# ImprovedBlackPill.net
KiCad netlist of a schematic drawn in Altium Designer
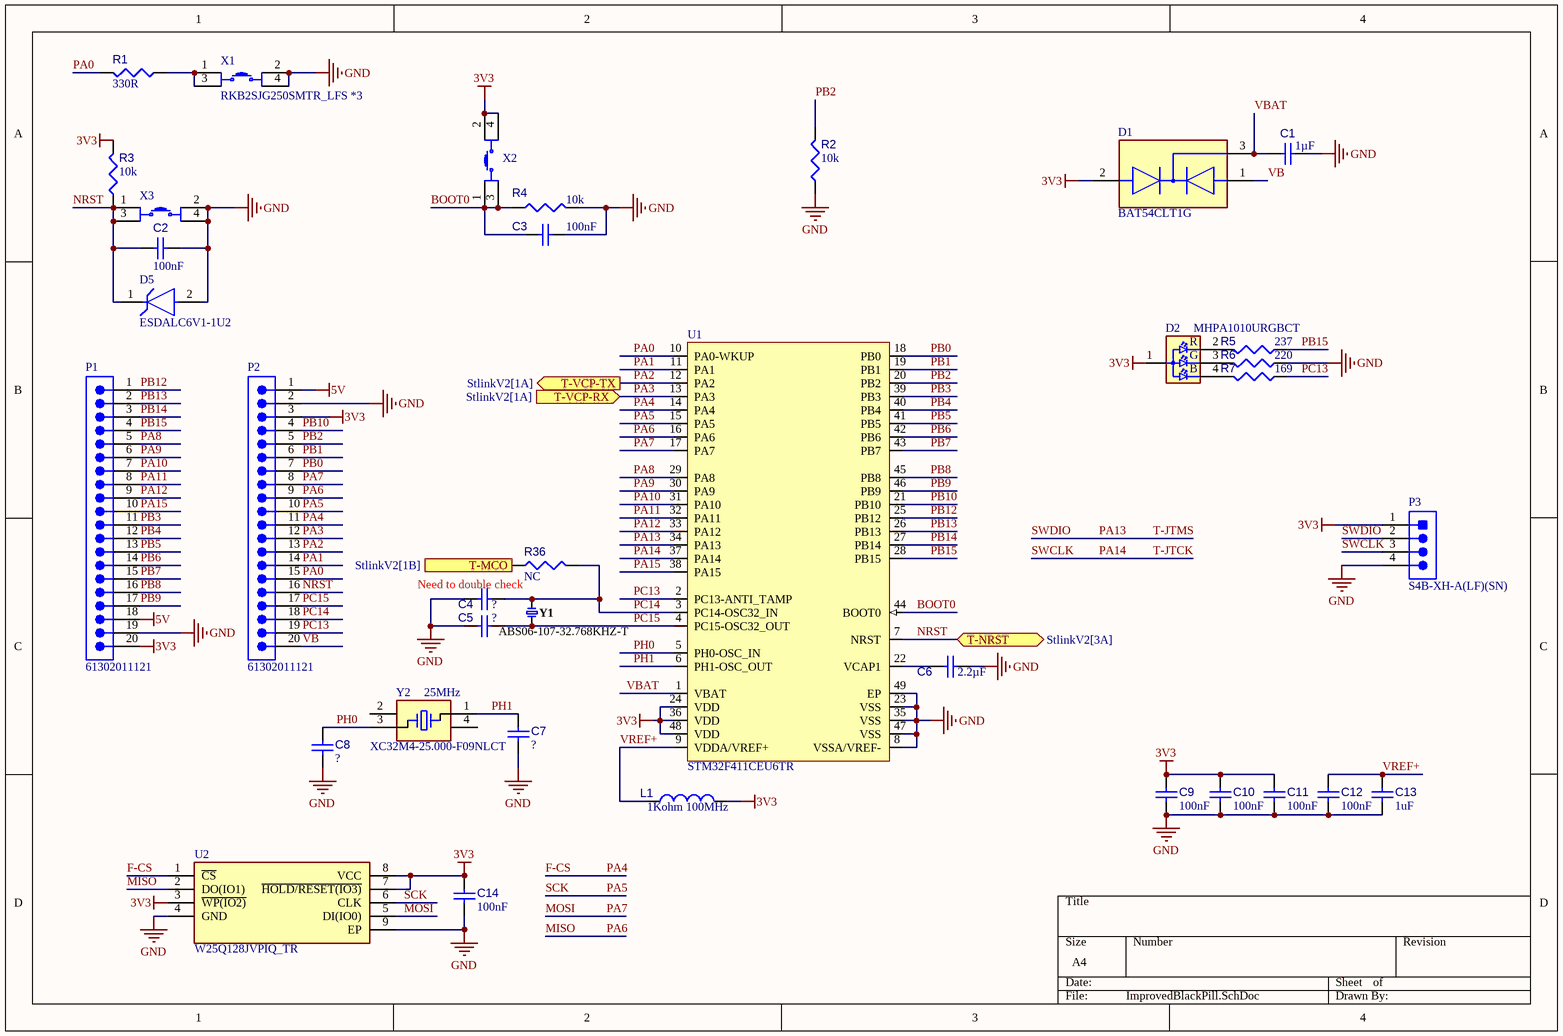
[diagram p0: ImprovedBlackPill.SchDoc]

(export (version "E")
  (design (tool "Eeschema 10.0.6"))
  (components
    (comp (ref "C1")
      (value "1µF")
      (footprint "CAPC1005X55X25ML05T10")
      (description "Chip Capacitor, 1 uF, +/- 10%, 6.3 V, 0402 (1005 Metric)")
      (fields (field (name "TOLERANCE") "10%") (field (name "Comment") "Capacitor 1 uF +/- 10% 6.3 V 0402"))
      (libsource (lib "Fei Han") (part "CAP-NP-2"))
    )
    (comp (ref "C2")
      (value "100nF")
      (footprint "CAPC1005X55X25ML05T05")
      (description "Chip Capacitor, 10 pF, +/- 5%, 50 V, 0402 (1005 Metric)")
      (fields (field (name "TOLERANCE") "5%") (field (name "Comment") "Capacitor 10 pF +/- 5% 50 V 0402"))
      (libsource (lib "Fei Han") (part "CAP-NP-2"))
    )
    (comp (ref "C3")
      (value "100nF")
      (footprint "CAPC1005X55X25ML05T05")
      (description "Chip Capacitor, 10 pF, +/- 5%, 50 V, 0402 (1005 Metric)")
      (fields (field (name "TOLERANCE") "5%") (field (name "Comment") "Capacitor 10 pF +/- 5% 50 V 0402"))
      (libsource (lib "Fei Han") (part "CAP-NP-2"))
    )
    (comp (ref "C4")
      (value "?")
      (footprint "CAPC1005X55X25ML05T05")
      (description "Chip Capacitor, 10 pF, +/- 5%, 50 V, 0402 (1005 Metric)")
      (fields (field (name "TOLERANCE") "5%") (field (name "Comment") "Capacitor 10 pF +/- 5% 50 V 0402"))
      (libsource (lib "Fei Han") (part "CAP-NP-2"))
    )
    (comp (ref "C5")
      (value "?")
      (footprint "CAPC1005X55X25ML05T05")
      (description "Chip Capacitor, 10 pF, +/- 5%, 50 V, 0402 (1005 Metric)")
      (fields (field (name "TOLERANCE") "5%") (field (name "Comment") "Capacitor 10 pF +/- 5% 50 V 0402"))
      (libsource (lib "Fei Han") (part "CAP-NP-2"))
    )
    (comp (ref "C6")
      (value "2.2µF")
      (footprint "CAPC2013X135X45NL10T25")
      (description "Chip Capacitor, 1 uF, +/- 10%, 50 V, 0805 (2012 Metric)")
      (fields (field (name "TOLERANCE") "10%") (field (name "Comment") "Capacitor 1 uF +/- 10% 50 V 0805"))
      (libsource (lib "Fei Han") (part "CAP-NP-2"))
    )
    (comp (ref "C7")
      (value "?")
      (footprint "CAPC1005X55X25ML05T05")
      (description "Chip Capacitor, 10 pF, +/- 5%, 50 V, 0402 (1005 Metric)")
      (fields (field (name "TOLERANCE") "5%") (field (name "Comment") "Capacitor 10 pF +/- 5% 50 V 0402"))
      (libsource (lib "Fei Han") (part "CAP-NP-2"))
    )
    (comp (ref "C8")
      (value "?")
      (footprint "CAPC1005X55X25ML05T05")
      (description "Chip Capacitor, 10 pF, +/- 5%, 50 V, 0402 (1005 Metric)")
      (fields (field (name "TOLERANCE") "5%") (field (name "Comment") "Capacitor 10 pF +/- 5% 50 V 0402"))
      (libsource (lib "Fei Han") (part "CAP-NP-2"))
    )
    (comp (ref "C9")
      (value "100nF")
      (footprint "CAPC1005X55X25ML05T05")
      (description "Chip Capacitor, 10 pF, +/- 5%, 50 V, 0402 (1005 Metric)")
      (fields (field (name "TOLERANCE") "5%") (field (name "Comment") "Capacitor 10 pF +/- 5% 50 V 0402"))
      (libsource (lib "Fei Han") (part "CAP-NP-2"))
    )
    (comp (ref "C10")
      (value "100nF")
      (footprint "CAPC1005X55X25ML05T05")
      (description "Chip Capacitor, 10 pF, +/- 5%, 50 V, 0402 (1005 Metric)")
      (fields (field (name "TOLERANCE") "5%") (field (name "Comment") "Capacitor 10 pF +/- 5% 50 V 0402"))
      (libsource (lib "Fei Han") (part "CAP-NP-2"))
    )
    (comp (ref "C11")
      (value "100nF")
      (footprint "CAPC1005X55X25ML05T05")
      (description "Chip Capacitor, 10 pF, +/- 5%, 50 V, 0402 (1005 Metric)")
      (fields (field (name "TOLERANCE") "5%") (field (name "Comment") "Capacitor 10 pF +/- 5% 50 V 0402"))
      (libsource (lib "Fei Han") (part "CAP-NP-2"))
    )
    (comp (ref "C12")
      (value "100nF")
      (footprint "CAPC1005X55X25ML05T05")
      (description "Chip Capacitor, 10 pF, +/- 5%, 50 V, 0402 (1005 Metric)")
      (fields (field (name "TOLERANCE") "5%") (field (name "Comment") "Capacitor 10 pF +/- 5% 50 V 0402"))
      (libsource (lib "Fei Han") (part "CAP-NP-2"))
    )
    (comp (ref "C13")
      (value "1uF")
      (footprint "CAPC1005X55X25ML05T05")
      (description "Chip Capacitor, 10 pF, +/- 5%, 50 V, 0402 (1005 Metric)")
      (fields (field (name "TOLERANCE") "5%") (field (name "Comment") "Capacitor 10 pF +/- 5% 50 V 0402"))
      (libsource (lib "Fei Han") (part "CAP-NP-2"))
    )
    (comp (ref "C14")
      (value "100nF")
      (footprint "CAPC1005X55X25ML05T05")
      (description "Chip Capacitor, 10 pF, +/- 5%, 50 V, 0402 (1005 Metric)")
      (fields (field (name "TOLERANCE") "5%") (field (name "Comment") "Capacitor 10 pF +/- 5% 50 V 0402"))
      (libsource (lib "Fei Han") (part "CAP-NP-2"))
    )
    (comp (ref "D1")
      (value "BAT54CLT1G")
      (footprint "FP-318-08-IPC_C")
      (description "Rectifier Diode, Schottky, 2 Element, 0.1A, 30V V(RRM), Silicon, TO-236")
      (libsource (lib "Fei Han") (part "f3b1224724dec1fb261d3e99a2bbfb6"))
    )
    (comp (ref "D2")
      (value "MHPA1010URGBCT")
      (footprint "FP-SML-LX0404SIUPGUSB-MFG")
      (libsource (lib "Fei Han") (part "2e8871f6955a40d35a6a753e53ead77"))
    )
    (comp (ref "D5")
      (value "ESDALC6V1-1U2")
      (footprint "FP-ST0201-MFG")
      (description "Trans Voltage Suppressor Diode, 20W, Unidirectional, 1 Element, Silicon")
      (libsource (lib "Fei Han") (part "f813f71cba58e380607f5dd3caf9714"))
    )
    (comp (ref "L1")
      (value "1Kohm 100MHz")
      (footprint "MURA-LQP15MN3N6B02D-2_N")
      (description "Inductor, 500 MHz, 170 mA, 0.5 Ohm, -40 to 85 degC, 01005 (0402 Metric), RoHS, Tape and Reel")
      (fields (field (name "MANUFACTURER") "Murata") (field (name "Comment") "LQP15MN3N6B02D"))
      (libsource (lib "Fei Han") (part "IND-2"))
    )
    (comp (ref "P1")
      (value "61302011121")
      (footprint "61302011121")
      (libsource (lib "Fei Han") (part "Header_Male_1R_20P"))
    )
    (comp (ref "P2")
      (value "61302011121")
      (footprint "61302011121")
      (libsource (lib "Fei Han") (part "Header_Male_1R_20P"))
    )
    (comp (ref "P3")
      (value "S4B-XH-A(LF)(SN)")
      (footprint "JST-S4B-XH-A(LF)(SN)_V")
      (fields (field (name "MANUFACTURER") "JST"))
      (libsource (lib "Fei Han") (part "CN-1P-M-R4"))
    )
    (comp (ref "R1")
      (value "330R")
      (footprint "RESC1005X40X25ML10T10")
      (description "Chip Resistor, 15 KOhm, +/- 1%, 0.063 W, -55 to 155 degC, 0402 (1005 Metric)")
      (fields (field (name "POWER") "63mW") (field (name "TOLERANCE") "1%"))
      (libsource (lib "Fei Han") (part "RES-2"))
    )
    (comp (ref "R2")
      (value "10k")
      (footprint "RESC1005X40X25ML10T10")
      (description "Chip Resistor, 15 KOhm, +/- 1%, 0.063 W, -55 to 155 degC, 0402 (1005 Metric)")
      (fields (field (name "POWER") "63mW") (field (name "TOLERANCE") "1%"))
      (libsource (lib "Fei Han") (part "RES-2"))
    )
    (comp (ref "R3")
      (value "10k")
      (footprint "RESC1005X40X25ML10T10")
      (description "Chip Resistor, 15 KOhm, +/- 1%, 0.063 W, -55 to 155 degC, 0402 (1005 Metric)")
      (fields (field (name "POWER") "63mW") (field (name "TOLERANCE") "1%"))
      (libsource (lib "Fei Han") (part "RES-2"))
    )
    (comp (ref "R4")
      (value "10k")
      (footprint "RESC1005X40X25ML10T10")
      (description "Chip Resistor, 15 KOhm, +/- 1%, 0.063 W, -55 to 155 degC, 0402 (1005 Metric)")
      (fields (field (name "POWER") "63mW") (field (name "TOLERANCE") "1%"))
      (libsource (lib "Fei Han") (part "RES-2"))
    )
    (comp (ref "R5")
      (value "237")
      (footprint "RESC1005X40X25ML10T10")
      (description "Chip Resistor, 15 KOhm, +/- 1%, 0.063 W, -55 to 155 degC, 0402 (1005 Metric)")
      (fields (field (name "POWER") "63mW") (field (name "TOLERANCE") "1%"))
      (libsource (lib "Fei Han") (part "RES-2"))
    )
    (comp (ref "R6")
      (value "220")
      (footprint "RESC1005X40X25ML10T10")
      (description "Chip Resistor, 15 KOhm, +/- 1%, 0.063 W, -55 to 155 degC, 0402 (1005 Metric)")
      (fields (field (name "POWER") "63mW") (field (name "TOLERANCE") "1%"))
      (libsource (lib "Fei Han") (part "RES-2"))
    )
    (comp (ref "R7")
      (value "169")
      (footprint "RESC1005X40X25ML10T10")
      (description "Chip Resistor, 15 KOhm, +/- 1%, 0.063 W, -55 to 155 degC, 0402 (1005 Metric)")
      (fields (field (name "POWER") "63mW") (field (name "TOLERANCE") "1%"))
      (libsource (lib "Fei Han") (part "RES-2"))
    )
    (comp (ref "R36")
      (value "NC")
      (footprint "RESC0402(1005)_L")
      (description "Jumper 0402")
      (libsource (lib "Fei Han") (part "RES-2"))
    )
    (comp (ref "U1")
      (value "STM32F411CEU6TR")
      (footprint "STM-UFQFPN48_N")
      (description "RISC Microcontroller, 32-Bit, FLASH, CORTEX-M4 CPU, 100MHz, CMOS")
      (libsource (lib "Fei Han") (part "STM32F411CEU6TR-Symbol-1"))
    )
    (comp (ref "U2")
      (value "W25Q128JVPIQ_TR")
      (footprint "SON127P600X500X80-9N-D")
      (description "NOR Flash spiFlash, 3V, 128M-bit, 4Kb Uniform Sector")
      (fields
        (field (name "MANUFACTURER_PART_NUMBER") "W25Q128JVPIQ TR")
        (field (name "MOUSER PART NUMBER") "454-W25Q128JVPIQTR")
      )
      (libsource (lib "Fei Han") (part "W25Q128JVPIQ_TR"))
    )
    (comp (ref "X1")
      (value "RKB2SJG250SMTR_LFS *3")
      (footprint "RKB2SJG250SMTRLFS")
      (description "Tactile Switches J Bend SMT Term 400gf Force")
      (fields
        (field (name "MOUSER PART NUMBER") "611-RKB2SJG250SMTRLF")
        (field (name "MANUFACTURER_PART_NUMBER") "RKB2SJG250SMTR LFS")
      )
      (libsource (lib "Fei Han") (part "RKB2SJG250SMTR_LFS"))
    )
    (comp (ref "X2")
      (value "RKB2SJG250SMTR_LFS")
      (footprint "RKB2SJG250SMTRLFS")
      (description "Tactile Switches J Bend SMT Term 400gf Force")
      (fields
        (field (name "MOUSER PART NUMBER") "611-RKB2SJG250SMTRLF")
        (field (name "MANUFACTURER_PART_NUMBER") "RKB2SJG250SMTR LFS")
      )
      (libsource (lib "Fei Han") (part "RKB2SJG250SMTR_LFS"))
    )
    (comp (ref "X3")
      (value "RKB2SJG250SMTR_LFS")
      (footprint "RKB2SJG250SMTRLFS")
      (description "Tactile Switches J Bend SMT Term 400gf Force")
      (fields
        (field (name "MOUSER PART NUMBER") "611-RKB2SJG250SMTRLF")
        (field (name "MANUFACTURER_PART_NUMBER") "RKB2SJG250SMTR LFS")
      )
      (libsource (lib "Fei Han") (part "RKB2SJG250SMTR_LFS"))
    )
    (comp (ref "Y1")
      (value "ABS06-107-32.768KHZ-T")
      (footprint "FP-ABS06-MFG")
      (description "Parallel - Fundamental Quartz Crystal, 0.032768MHz Nom")
      (libsource (lib "Fei Han") (part "XTAL-2"))
    )
    (comp (ref "Y2")
      (value "XC32M4-25.000-F09NLCT")
      (footprint "830105863709")
      (description "XC32M4-25.000-F09NLCT Cload 9pF")
      (libsource (lib "Fei Han") (part "830105863709"))
    )
  )
  (nets
    (net (code "2") (name "/BOOT0") (class "Default")
      (node (ref "C3") (pin "1") (pinfunction "1_1") (pintype "passive"))
      (node (ref "R4") (pin "1") (pinfunction "1_1") (pintype "passive"))
      (node (ref "U1") (pin "44") (pinfunction "BOOT0_44") (pintype "input"))
      (node (ref "X2") (pin "1") (pinfunction "COM_1_1") (pintype "passive"))
      (node (ref "X2") (pin "3") (pinfunction "NO_1_3") (pintype "passive"))
    )
    (net (code "3") (name "/F-CS") (class "Default")
      (node (ref "P2") (pin "11") (pinfunction "11_11") (pintype "passive"))
      (node (ref "U1") (pin "14") (pinfunction "PA4_14") (pintype "bidirectional"))
      (node (ref "U2") (pin "1") (pinfunction "~{CS}_1") (pintype "passive"))
    )
    (net (code "4") (name "/MISO") (class "Default")
      (node (ref "P2") (pin "9") (pinfunction "9_9") (pintype "passive"))
      (node (ref "U1") (pin "16") (pinfunction "PA6_16") (pintype "bidirectional"))
      (node (ref "U2") (pin "2") (pinfunction "DO(IO1)_2") (pintype "passive"))
    )
    (net (code "5") (name "/MOSI") (class "Default")
      (node (ref "P2") (pin "8") (pinfunction "8_8") (pintype "passive"))
      (node (ref "U1") (pin "17") (pinfunction "PA7_17") (pintype "bidirectional"))
      (node (ref "U2") (pin "5") (pinfunction "DI(IO0)_5") (pintype "passive"))
    )
    (net (code "6") (name "/NRST") (class "Default")
      (node (ref "C2") (pin "1") (pinfunction "1_1") (pintype "passive"))
      (node (ref "D5") (pin "1") (pinfunction "C_1") (pintype "passive"))
      (node (ref "P2") (pin "16") (pinfunction "16_16") (pintype "passive"))
      (node (ref "R3") (pin "1") (pinfunction "1_1") (pintype "passive"))
      (node (ref "U1") (pin "7") (pinfunction "NRST_7") (pintype "bidirectional"))
      (node (ref "X3") (pin "1") (pinfunction "COM_1_1") (pintype "passive"))
      (node (ref "X3") (pin "3") (pinfunction "NO_1_3") (pintype "passive"))
    )
    (net (code "7") (name "/PA0") (class "Default")
      (node (ref "P2") (pin "15") (pinfunction "15_15") (pintype "passive"))
      (node (ref "R1") (pin "2") (pinfunction "2_2") (pintype "passive"))
      (node (ref "U1") (pin "10") (pinfunction "PA0-WKUP_10") (pintype "bidirectional"))
    )
    (net (code "8") (name "/PA1") (class "Default")
      (node (ref "P2") (pin "14") (pinfunction "14_14") (pintype "passive"))
      (node (ref "U1") (pin "11") (pinfunction "PA1_11") (pintype "bidirectional"))
    )
    (net (code "9") (name "/PA2") (class "Default")
      (node (ref "P2") (pin "13") (pinfunction "13_13") (pintype "passive"))
      (node (ref "U1") (pin "12") (pinfunction "PA2_12") (pintype "bidirectional"))
    )
    (net (code "10") (name "/PA3") (class "Default")
      (node (ref "P2") (pin "12") (pinfunction "12_12") (pintype "passive"))
      (node (ref "U1") (pin "13") (pinfunction "PA3_13") (pintype "bidirectional"))
    )
    (net (code "11") (name "/PA5") (class "Default")
      (node (ref "P2") (pin "10") (pinfunction "10_10") (pintype "passive"))
      (node (ref "U1") (pin "15") (pinfunction "PA5_15") (pintype "bidirectional"))
      (node (ref "U2") (pin "6") (pinfunction "CLK_6") (pintype "passive"))
    )
    (net (code "12") (name "/PA8") (class "Default")
      (node (ref "P1") (pin "5") (pinfunction "5_5") (pintype "passive"))
      (node (ref "U1") (pin "29") (pinfunction "PA8_29") (pintype "bidirectional"))
    )
    (net (code "13") (name "/PA9") (class "Default")
      (node (ref "P1") (pin "6") (pinfunction "6_6") (pintype "passive"))
      (node (ref "U1") (pin "30") (pinfunction "PA9_30") (pintype "bidirectional"))
    )
    (net (code "14") (name "/PA10") (class "Default")
      (node (ref "P1") (pin "7") (pinfunction "7_7") (pintype "passive"))
      (node (ref "U1") (pin "31") (pinfunction "PA10_31") (pintype "bidirectional"))
    )
    (net (code "15") (name "/PA11") (class "Default")
      (node (ref "P1") (pin "8") (pinfunction "8_8") (pintype "passive"))
      (node (ref "U1") (pin "32") (pinfunction "PA11_32") (pintype "bidirectional"))
    )
    (net (code "16") (name "/PA12") (class "Default")
      (node (ref "P1") (pin "9") (pinfunction "9_9") (pintype "passive"))
      (node (ref "U1") (pin "33") (pinfunction "PA12_33") (pintype "bidirectional"))
    )
    (net (code "17") (name "/PA13") (class "Default")
      (node (ref "P3") (pin "2") (pinfunction "2_2") (pintype "passive"))
      (node (ref "U1") (pin "34") (pinfunction "PA13_34") (pintype "bidirectional"))
    )
    (net (code "18") (name "/PA14") (class "Default")
      (node (ref "P3") (pin "3") (pinfunction "3_3") (pintype "passive"))
      (node (ref "U1") (pin "37") (pinfunction "PA14_37") (pintype "bidirectional"))
    )
    (net (code "19") (name "/PA15") (class "Default")
      (node (ref "P1") (pin "10") (pinfunction "10_10") (pintype "passive"))
      (node (ref "U1") (pin "38") (pinfunction "PA15_38") (pintype "bidirectional"))
    )
    (net (code "20") (name "/PB0") (class "Default")
      (node (ref "P2") (pin "7") (pinfunction "7_7") (pintype "passive"))
      (node (ref "U1") (pin "18") (pinfunction "PB0_18") (pintype "bidirectional"))
    )
    (net (code "21") (name "/PB1") (class "Default")
      (node (ref "P2") (pin "6") (pinfunction "6_6") (pintype "passive"))
      (node (ref "U1") (pin "19") (pinfunction "PB1_19") (pintype "bidirectional"))
    )
    (net (code "22") (name "/PB2") (class "Default")
      (node (ref "P2") (pin "5") (pinfunction "5_5") (pintype "passive"))
      (node (ref "R2") (pin "2") (pinfunction "2_2") (pintype "passive"))
      (node (ref "U1") (pin "20") (pinfunction "PB2_20") (pintype "bidirectional"))
    )
    (net (code "23") (name "/PB3") (class "Default")
      (node (ref "P1") (pin "11") (pinfunction "11_11") (pintype "passive"))
      (node (ref "U1") (pin "39") (pinfunction "PB3_39") (pintype "bidirectional"))
    )
    (net (code "24") (name "/PB4") (class "Default")
      (node (ref "P1") (pin "12") (pinfunction "12_12") (pintype "passive"))
      (node (ref "U1") (pin "40") (pinfunction "PB4_40") (pintype "bidirectional"))
    )
    (net (code "25") (name "/PB5") (class "Default")
      (node (ref "P1") (pin "13") (pinfunction "13_13") (pintype "passive"))
      (node (ref "U1") (pin "41") (pinfunction "PB5_41") (pintype "bidirectional"))
    )
    (net (code "26") (name "/PB6") (class "Default")
      (node (ref "P1") (pin "14") (pinfunction "14_14") (pintype "passive"))
      (node (ref "U1") (pin "42") (pinfunction "PB6_42") (pintype "bidirectional"))
    )
    (net (code "27") (name "/PB7") (class "Default")
      (node (ref "P1") (pin "15") (pinfunction "15_15") (pintype "passive"))
      (node (ref "U1") (pin "43") (pinfunction "PB7_43") (pintype "bidirectional"))
    )
    (net (code "28") (name "/PB8") (class "Default")
      (node (ref "P1") (pin "16") (pinfunction "16_16") (pintype "passive"))
      (node (ref "U1") (pin "45") (pinfunction "PB8_45") (pintype "bidirectional"))
    )
    (net (code "29") (name "/PB9") (class "Default")
      (node (ref "P1") (pin "17") (pinfunction "17_17") (pintype "passive"))
      (node (ref "U1") (pin "46") (pinfunction "PB9_46") (pintype "bidirectional"))
    )
    (net (code "30") (name "/PB10") (class "Default")
      (node (ref "P2") (pin "4") (pinfunction "4_4") (pintype "passive"))
      (node (ref "U1") (pin "21") (pinfunction "PB10_21") (pintype "bidirectional"))
    )
    (net (code "31") (name "/PB12") (class "Default")
      (node (ref "P1") (pin "1") (pinfunction "1_1") (pintype "passive"))
      (node (ref "U1") (pin "25") (pinfunction "PB12_25") (pintype "bidirectional"))
    )
    (net (code "32") (name "/PB13") (class "Default")
      (node (ref "P1") (pin "2") (pinfunction "2_2") (pintype "passive"))
      (node (ref "U1") (pin "26") (pinfunction "PB13_26") (pintype "bidirectional"))
    )
    (net (code "33") (name "/PB14") (class "Default")
      (node (ref "P1") (pin "3") (pinfunction "3_3") (pintype "passive"))
      (node (ref "U1") (pin "27") (pinfunction "PB14_27") (pintype "bidirectional"))
    )
    (net (code "34") (name "/PB15") (class "Default")
      (node (ref "P1") (pin "4") (pinfunction "4_4") (pintype "passive"))
      (node (ref "R5") (pin "1") (pinfunction "1_1") (pintype "passive"))
      (node (ref "U1") (pin "28") (pinfunction "PB15_28") (pintype "bidirectional"))
    )
    (net (code "35") (name "/PC13") (class "Default")
      (node (ref "P2") (pin "19") (pinfunction "19_19") (pintype "passive"))
      (node (ref "R7") (pin "1") (pinfunction "1_1") (pintype "passive"))
      (node (ref "U1") (pin "2") (pinfunction "PC13-ANTI_TAMP_2") (pintype "bidirectional"))
    )
    (net (code "36") (name "/PC14") (class "Default")
      (node (ref "C4") (pin "2") (pinfunction "2_2") (pintype "passive"))
      (node (ref "P2") (pin "18") (pinfunction "18_18") (pintype "passive"))
      (node (ref "R36") (pin "2") (pinfunction "2_2") (pintype "passive"))
      (node (ref "U1") (pin "3") (pinfunction "PC14-OSC32_IN_3") (pintype "bidirectional"))
      (node (ref "Y1") (pin "2") (pinfunction "2_2") (pintype "passive"))
    )
    (net (code "37") (name "/PC15") (class "Default")
      (node (ref "C5") (pin "2") (pinfunction "2_2") (pintype "passive"))
      (node (ref "P2") (pin "17") (pinfunction "17_17") (pintype "passive"))
      (node (ref "U1") (pin "4") (pinfunction "PC15-OSC32_OUT_4") (pintype "bidirectional"))
      (node (ref "Y1") (pin "1") (pinfunction "1_1") (pintype "passive"))
    )
    (net (code "38") (name "/PH0") (class "Default")
      (node (ref "C8") (pin "2") (pinfunction "2_2") (pintype "passive"))
      (node (ref "U1") (pin "5") (pinfunction "PH0-OSC_IN_5") (pintype "bidirectional"))
      (node (ref "Y2") (pin "3") (pinfunction "CRYSTAL__2_3") (pintype "passive"))
    )
    (net (code "39") (name "/PH1") (class "Default")
      (node (ref "C7") (pin "2") (pinfunction "2_2") (pintype "passive"))
      (node (ref "U1") (pin "6") (pinfunction "PH1-OSC_OUT_6") (pintype "bidirectional"))
      (node (ref "Y2") (pin "1") (pinfunction "CRYSTAL__1_1") (pintype "passive"))
    )
    (net (code "40") (name "/T-MCO") (class "Default")
      (node (ref "R36") (pin "1") (pinfunction "1_1") (pintype "passive"))
    )
    (net (code "41") (name "/VB") (class "Default")
      (node (ref "D1") (pin "1") (pinfunction "1_ANODE_1") (pintype "passive"))
      (node (ref "P2") (pin "20") (pinfunction "20_20") (pintype "passive"))
    )
    (net (code "42") (name "/VBAT") (class "Default")
      (node (ref "C1") (pin "1") (pinfunction "1_1") (pintype "passive"))
      (node (ref "D1") (pin "3") (pinfunction "C_3") (pintype "passive"))
      (node (ref "U1") (pin "1") (pinfunction "VBAT_1") (pintype "power_in"))
    )
    (net (code "43") (name "/VREF+") (class "Default")
      (node (ref "C12") (pin "2") (pinfunction "2_2") (pintype "passive"))
      (node (ref "C13") (pin "2") (pinfunction "2_2") (pintype "passive"))
      (node (ref "L1") (pin "2") (pinfunction "2_2") (pintype "passive"))
      (node (ref "U1") (pin "9") (pinfunction "VDDA/VREF+_9") (pintype "passive"))
    )
    (net (code "44") (name "3V3") (class "Default")
      (node (ref "C10") (pin "2") (pinfunction "2_2") (pintype "passive"))
      (node (ref "C11") (pin "2") (pinfunction "2_2") (pintype "passive"))
      (node (ref "C14") (pin "2") (pinfunction "2_2") (pintype "passive"))
      (node (ref "C9") (pin "2") (pinfunction "2_2") (pintype "passive"))
      (node (ref "D1") (pin "2") (pinfunction "2_ANODE_2") (pintype "passive"))
      (node (ref "D2") (pin "1") (pinfunction "Common_Anode_1") (pintype "passive"))
      (node (ref "L1") (pin "1") (pinfunction "1_1") (pintype "passive"))
      (node (ref "P1") (pin "20") (pinfunction "20_20") (pintype "passive"))
      (node (ref "P2") (pin "3") (pinfunction "3_3") (pintype "passive"))
      (node (ref "P3") (pin "1") (pinfunction "1_1") (pintype "passive"))
      (node (ref "R3") (pin "2") (pinfunction "2_2") (pintype "passive"))
      (node (ref "U1") (pin "24") (pinfunction "VDD_24") (pintype "power_in"))
      (node (ref "U1") (pin "36") (pinfunction "VDD_36") (pintype "power_in"))
      (node (ref "U1") (pin "48") (pinfunction "VDD_48") (pintype "passive"))
      (node (ref "U2") (pin "3") (pinfunction "~{WP(IO2)}_3") (pintype "passive"))
      (node (ref "U2") (pin "7") (pinfunction "~{HOLD/RESET(IO3)}_7") (pintype "passive"))
      (node (ref "U2") (pin "8") (pinfunction "VCC_8") (pintype "passive"))
      (node (ref "X2") (pin "2") (pinfunction "COM_2_2") (pintype "passive"))
      (node (ref "X2") (pin "4") (pinfunction "NO_2_4") (pintype "passive"))
    )
    (net (code "45") (name "5V") (class "Default")
      (node (ref "P1") (pin "18") (pinfunction "18_18") (pintype "passive"))
      (node (ref "P2") (pin "1") (pinfunction "1_1") (pintype "passive"))
    )
    (net (code "46") (name "GND") (class "Default")
      (node (ref "C1") (pin "2") (pinfunction "2_2") (pintype "passive"))
      (node (ref "C10") (pin "1") (pinfunction "1_1") (pintype "passive"))
      (node (ref "C11") (pin "1") (pinfunction "1_1") (pintype "passive"))
      (node (ref "C12") (pin "1") (pinfunction "1_1") (pintype "passive"))
      (node (ref "C13") (pin "1") (pinfunction "1_1") (pintype "passive"))
      (node (ref "C14") (pin "1") (pinfunction "1_1") (pintype "passive"))
      (node (ref "C2") (pin "2") (pinfunction "2_2") (pintype "passive"))
      (node (ref "C3") (pin "2") (pinfunction "2_2") (pintype "passive"))
      (node (ref "C4") (pin "1") (pinfunction "1_1") (pintype "passive"))
      (node (ref "C5") (pin "1") (pinfunction "1_1") (pintype "passive"))
      (node (ref "C6") (pin "2") (pinfunction "2_2") (pintype "passive"))
      (node (ref "C7") (pin "1") (pinfunction "1_1") (pintype "passive"))
      (node (ref "C8") (pin "1") (pinfunction "1_1") (pintype "passive"))
      (node (ref "C9") (pin "1") (pinfunction "1_1") (pintype "passive"))
      (node (ref "D5") (pin "2") (pinfunction "A_2") (pintype "passive"))
      (node (ref "P1") (pin "19") (pinfunction "19_19") (pintype "passive"))
      (node (ref "P2") (pin "2") (pinfunction "2_2") (pintype "passive"))
      (node (ref "P3") (pin "4") (pinfunction "4_4") (pintype "passive"))
      (node (ref "R2") (pin "1") (pinfunction "1_1") (pintype "passive"))
      (node (ref "R4") (pin "2") (pinfunction "2_2") (pintype "passive"))
      (node (ref "R6") (pin "1") (pinfunction "1_1") (pintype "passive"))
      (node (ref "U1") (pin "23") (pinfunction "VSS_23") (pintype "passive"))
      (node (ref "U1") (pin "35") (pinfunction "VSS_35") (pintype "passive"))
      (node (ref "U1") (pin "47") (pinfunction "VSS_47") (pintype "passive"))
      (node (ref "U1") (pin "49") (pinfunction "EP_49") (pintype "passive"))
      (node (ref "U1") (pin "8") (pinfunction "VSSA/VREF-_8") (pintype "passive"))
      (node (ref "U2") (pin "4") (pinfunction "GND_4") (pintype "passive"))
      (node (ref "U2") (pin "9") (pinfunction "EP_9") (pintype "passive"))
      (node (ref "X1") (pin "2") (pinfunction "COM_2_2") (pintype "passive"))
      (node (ref "X1") (pin "4") (pinfunction "NO_2_4") (pintype "passive"))
      (node (ref "X3") (pin "2") (pinfunction "COM_2_2") (pintype "passive"))
      (node (ref "X3") (pin "4") (pinfunction "NO_2_4") (pintype "passive"))
    )
    (net (code "47") (name "Net-(D2-B)") (class "Default")
      (node (ref "D2") (pin "4") (pinfunction "B_4") (pintype "passive"))
      (node (ref "R7") (pin "2") (pinfunction "2_2") (pintype "passive"))
    )
    (net (code "48") (name "Net-(D2-Blue_C)") (class "Default")
      (node (ref "D2") (pin "3") (pinfunction "Blue_C_3") (pintype "passive"))
      (node (ref "R6") (pin "2") (pinfunction "2_2") (pintype "passive"))
    )
    (net (code "49") (name "Net-(D2-Red_C)") (class "Default")
      (node (ref "D2") (pin "2") (pinfunction "Red_C_2") (pintype "passive"))
      (node (ref "R5") (pin "2") (pinfunction "2_2") (pintype "passive"))
    )
    (net (code "50") (name "Net-(U1-VCAP1)") (class "Default")
      (node (ref "C6") (pin "1") (pinfunction "1_1") (pintype "passive"))
      (node (ref "U1") (pin "22") (pinfunction "VCAP1_22") (pintype "passive"))
    )
    (net (code "51") (name "Net-(X1-COM_1)") (class "Default")
      (node (ref "R1") (pin "1") (pinfunction "1_1") (pintype "passive"))
      (node (ref "X1") (pin "1") (pinfunction "COM_1_1") (pintype "passive"))
      (node (ref "X1") (pin "3") (pinfunction "NO_1_3") (pintype "passive"))
    )
    (net (code "52") (name "unconnected-(Y2-GND_&_LID_1-Pad2)") (class "Default")
      (node (ref "Y2") (pin "2") (pinfunction "GND_&_LID_1_2") (pintype "passive"))
    )
    (net (code "53") (name "unconnected-(Y2-GND_&_LID_2-Pad4)") (class "Default")
      (node (ref "Y2") (pin "4") (pinfunction "GND_&_LID_2_4") (pintype "passive"))
    )
  )
)
